# Finale_Competition.net
KiCad netlist of a schematic drawn in Altium Designer
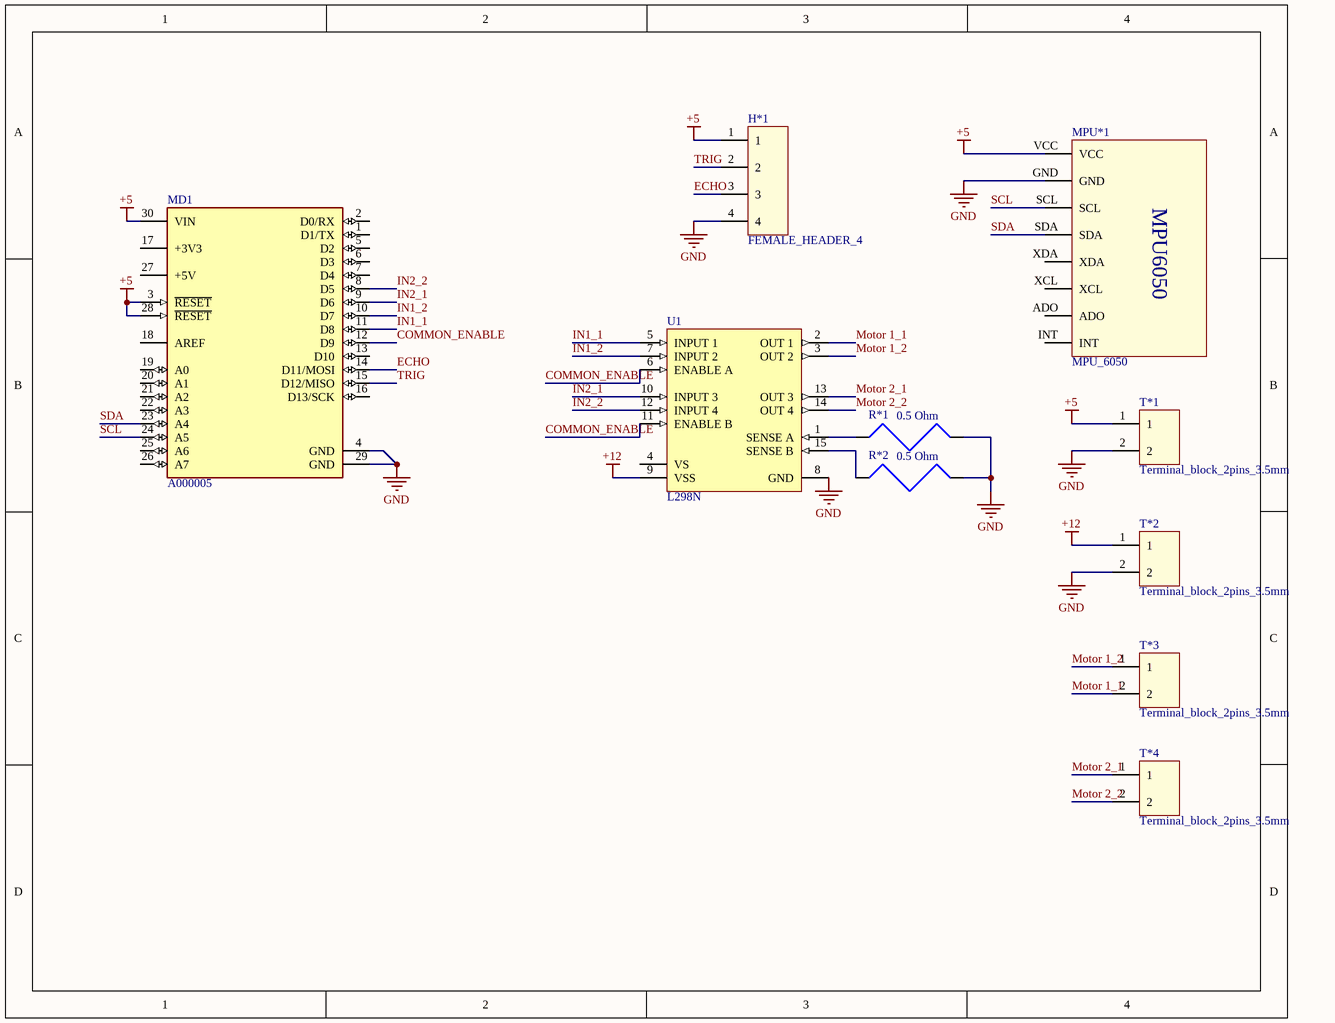
[diagram p0: Finale_Competition.SchDoc]

(export (version "E")
  (design (tool "Eeschema 10.0.6"))
  (components
    (comp (ref "H*1")
      (value "FEMALE_HEADER_4")
      (footprint "Female_Header_4")
      (libsource (lib "Mia_Training") (part "FEMALE_HEADER_4"))
    )
    (comp (ref "MD1")
      (value "A000005")
      (footprint "FP-A000005-MFG")
      (description "ARDUINO NANO ATMEGA328 EVAL BRD")
      (libsource (lib "Altium Content Vault") (part "d190c066e99afd1c6882cf92e11b2cc"))
    )
    (comp (ref "MPU*1")
      (value "MPU_6050")
      (footprint "MPU6050")
      (libsource (lib "Mia_Training") (part "MPU_6050"))
    )
    (comp (ref "R*1")
      (value "0.5 Ohm")
      (footprint "Resistor")
      (libsource (lib "Mia_Training") (part "Resistor"))
    )
    (comp (ref "R*2")
      (value "0.5 Ohm")
      (footprint "Resistor")
      (libsource (lib "Mia_Training") (part "Resistor"))
    )
    (comp (ref "T*1")
      (value "Terminal_block_2pins_3.5mm")
      (footprint "Terminal_block_2pins_3.5mm")
      (libsource (lib "Mia_Training") (part "Terminal_block_2pins_3.5mm"))
    )
    (comp (ref "T*2")
      (value "Terminal_block_2pins_3.5mm")
      (footprint "Terminal_block_2pins_3.5mm")
      (libsource (lib "Mia_Training") (part "Terminal_block_2pins_3.5mm"))
    )
    (comp (ref "T*3")
      (value "Terminal_block_2pins_3.5mm")
      (footprint "Terminal_block_2pins_3.5mm")
      (libsource (lib "Mia_Training") (part "Terminal_block_2pins_3.5mm"))
    )
    (comp (ref "T*4")
      (value "Terminal_block_2pins_3.5mm")
      (footprint "Terminal_block_2pins_3.5mm")
      (libsource (lib "Mia_Training") (part "Terminal_block_2pins_3.5mm"))
    )
    (comp (ref "U1")
      (value "L298N")
      (footprint "STM-FM-15")
      (description "Dual Full-Bridge Driver, 4.8 to 46 V, -40 to 150 degC, 15-Pin FM (MW 15L), RoHS, Tube")
      (fields (field (name "MANUFACTURER") "STMicroelectronics") (field (name "PARTNUMBER") "L298"))
      (libsource (lib "Altium Content Vault") (part "STM-L298-15"))
    )
  )
  (nets
    (net (code "1") (name "+5") (class "Default")
      (node (ref "H*1") (pin "1") (pinfunction "1_1") (pintype "passive"))
      (node (ref "MD1") (pin "28") (pinfunction "~{RESET}_28") (pintype "input"))
      (node (ref "MD1") (pin "3") (pinfunction "~{RESET}_3") (pintype "input"))
      (node (ref "MD1") (pin "30") (pinfunction "VIN_30") (pintype "power_in"))
      (node (ref "MPU*1") (pin "VCC") (pinfunction "VCC_VCC") (pintype "passive"))
      (node (ref "T*1") (pin "1") (pinfunction "1_1") (pintype "passive"))
    )
    (net (code "2") (name "+12") (class "Default")
      (node (ref "T*2") (pin "1") (pinfunction "1_1") (pintype "passive"))
      (node (ref "U1") (pin "9") (pinfunction "VSS_9") (pintype "power_in"))
    )
    (net (code "3") (name "/COMMON_ENABLE") (class "Default")
      (node (ref "MD1") (pin "12") (pinfunction "D9_12") (pintype "bidirectional"))
      (node (ref "U1") (pin "11") (pinfunction "ENABLE_B_11") (pintype "input"))
      (node (ref "U1") (pin "6") (pinfunction "ENABLE_A_6") (pintype "input"))
    )
    (net (code "4") (name "/ECHO") (class "Default")
      (node (ref "H*1") (pin "3") (pinfunction "3_3") (pintype "passive"))
      (node (ref "MD1") (pin "14") (pinfunction "D11/MOSI_14") (pintype "bidirectional"))
    )
    (net (code "5") (name "/IN1_1") (class "Default")
      (node (ref "MD1") (pin "11") (pinfunction "D8_11") (pintype "bidirectional"))
      (node (ref "U1") (pin "5") (pinfunction "INPUT_1_5") (pintype "input"))
    )
    (net (code "6") (name "/IN1_2") (class "Default")
      (node (ref "MD1") (pin "10") (pinfunction "D7_10") (pintype "bidirectional"))
      (node (ref "U1") (pin "7") (pinfunction "INPUT_2_7") (pintype "input"))
    )
    (net (code "7") (name "/IN2_1") (class "Default")
      (node (ref "MD1") (pin "9") (pinfunction "D6_9") (pintype "bidirectional"))
      (node (ref "U1") (pin "10") (pinfunction "INPUT_3_10") (pintype "input"))
    )
    (net (code "8") (name "/IN2_2") (class "Default")
      (node (ref "MD1") (pin "8") (pinfunction "D5_8") (pintype "bidirectional"))
      (node (ref "U1") (pin "12") (pinfunction "INPUT_4_12") (pintype "input"))
    )
    (net (code "9") (name "/Motor 1_1") (class "Default")
      (node (ref "T*3") (pin "2") (pinfunction "2_2") (pintype "passive"))
      (node (ref "U1") (pin "2") (pinfunction "OUT_1_2") (pintype "output"))
    )
    (net (code "10") (name "/Motor 1_2") (class "Default")
      (node (ref "T*3") (pin "1") (pinfunction "1_1") (pintype "passive"))
      (node (ref "U1") (pin "3") (pinfunction "OUT_2_3") (pintype "output"))
    )
    (net (code "11") (name "/Motor 2_1") (class "Default")
      (node (ref "T*4") (pin "1") (pinfunction "1_1") (pintype "passive"))
      (node (ref "U1") (pin "13") (pinfunction "OUT_3_13") (pintype "output"))
    )
    (net (code "12") (name "/Motor 2_2") (class "Default")
      (node (ref "T*4") (pin "2") (pinfunction "2_2") (pintype "passive"))
      (node (ref "U1") (pin "14") (pinfunction "OUT_4_14") (pintype "output"))
    )
    (net (code "13") (name "/SCL") (class "Default")
      (node (ref "MD1") (pin "24") (pinfunction "A5_24") (pintype "bidirectional"))
      (node (ref "MPU*1") (pin "SCL") (pinfunction "SCL_SCL") (pintype "passive"))
    )
    (net (code "14") (name "/SDA") (class "Default")
      (node (ref "MD1") (pin "23") (pinfunction "A4_23") (pintype "bidirectional"))
      (node (ref "MPU*1") (pin "SDA") (pinfunction "SDA_SDA") (pintype "passive"))
    )
    (net (code "15") (name "/TRIG") (class "Default")
      (node (ref "H*1") (pin "2") (pinfunction "2_2") (pintype "passive"))
      (node (ref "MD1") (pin "15") (pinfunction "D12/MISO_15") (pintype "bidirectional"))
    )
    (net (code "16") (name "GND") (class "Default")
      (node (ref "H*1") (pin "4") (pinfunction "4_4") (pintype "passive"))
      (node (ref "MD1") (pin "29") (pinfunction "GND_29") (pintype "power_in"))
      (node (ref "MD1") (pin "4") (pinfunction "GND_4") (pintype "power_in"))
      (node (ref "MPU*1") (pin "GND") (pinfunction "GND_GND") (pintype "passive"))
      (node (ref "R*1") (pin "2") (pinfunction "2_2") (pintype "passive"))
      (node (ref "R*2") (pin "2") (pinfunction "2_2") (pintype "passive"))
      (node (ref "T*1") (pin "2") (pinfunction "2_2") (pintype "passive"))
      (node (ref "T*2") (pin "2") (pinfunction "2_2") (pintype "passive"))
      (node (ref "U1") (pin "8") (pinfunction "GND_8") (pintype "power_in"))
    )
    (net (code "17") (name "Net-(U1-SENSE_A)") (class "Default")
      (node (ref "R*1") (pin "1") (pinfunction "1_1") (pintype "passive"))
      (node (ref "U1") (pin "1") (pinfunction "SENSE_A_1") (pintype "input"))
    )
    (net (code "18") (name "Net-(U1-SENSE_B)") (class "Default")
      (node (ref "R*2") (pin "1") (pinfunction "1_1") (pintype "passive"))
      (node (ref "U1") (pin "15") (pinfunction "SENSE_B_15") (pintype "input"))
    )
    (net (code "19") (name "unconnected-(MD1-+3V3-Pad17)") (class "Default")
      (node (ref "MD1") (pin "17") (pinfunction "+3V3_17") (pintype "power_in"))
    )
    (net (code "20") (name "unconnected-(MD1-+5V-Pad27)") (class "Default")
      (node (ref "MD1") (pin "27") (pinfunction "+5V_27") (pintype "power_in"))
    )
    (net (code "21") (name "unconnected-(MD1-A0-Pad19)") (class "Default")
      (node (ref "MD1") (pin "19") (pinfunction "A0_19") (pintype "bidirectional"))
    )
    (net (code "22") (name "unconnected-(MD1-A1-Pad20)") (class "Default")
      (node (ref "MD1") (pin "20") (pinfunction "A1_20") (pintype "bidirectional"))
    )
    (net (code "23") (name "unconnected-(MD1-A2-Pad21)") (class "Default")
      (node (ref "MD1") (pin "21") (pinfunction "A2_21") (pintype "bidirectional"))
    )
    (net (code "24") (name "unconnected-(MD1-A3-Pad22)") (class "Default")
      (node (ref "MD1") (pin "22") (pinfunction "A3_22") (pintype "bidirectional"))
    )
    (net (code "25") (name "unconnected-(MD1-A6-Pad25)") (class "Default")
      (node (ref "MD1") (pin "25") (pinfunction "A6_25") (pintype "bidirectional"))
    )
    (net (code "26") (name "unconnected-(MD1-A7-Pad26)") (class "Default")
      (node (ref "MD1") (pin "26") (pinfunction "A7_26") (pintype "bidirectional"))
    )
    (net (code "27") (name "unconnected-(MD1-AREF-Pad18)") (class "Default")
      (node (ref "MD1") (pin "18") (pinfunction "AREF_18") (pintype "passive"))
    )
    (net (code "28") (name "unconnected-(MD1-D0{slash}RX-Pad2)") (class "Default")
      (node (ref "MD1") (pin "2") (pinfunction "D0/RX_2") (pintype "bidirectional"))
    )
    (net (code "29") (name "unconnected-(MD1-D1{slash}TX-Pad1)") (class "Default")
      (node (ref "MD1") (pin "1") (pinfunction "D1/TX_1") (pintype "bidirectional"))
    )
    (net (code "30") (name "unconnected-(MD1-D2-Pad5)") (class "Default")
      (node (ref "MD1") (pin "5") (pinfunction "D2_5") (pintype "bidirectional"))
    )
    (net (code "31") (name "unconnected-(MD1-D3-Pad6)") (class "Default")
      (node (ref "MD1") (pin "6") (pinfunction "D3_6") (pintype "bidirectional"))
    )
    (net (code "32") (name "unconnected-(MD1-D4-Pad7)") (class "Default")
      (node (ref "MD1") (pin "7") (pinfunction "D4_7") (pintype "bidirectional"))
    )
    (net (code "33") (name "unconnected-(MD1-D10-Pad13)") (class "Default")
      (node (ref "MD1") (pin "13") (pinfunction "D10_13") (pintype "bidirectional"))
    )
    (net (code "34") (name "unconnected-(MD1-D13{slash}SCK-Pad16)") (class "Default")
      (node (ref "MD1") (pin "16") (pinfunction "D13/SCK_16") (pintype "bidirectional"))
    )
    (net (code "35") (name "unconnected-(MPU*1-PadADO)") (class "Default")
      (node (ref "MPU*1") (pin "ADO") (pinfunction "ADO_ADO") (pintype "passive"))
    )
    (net (code "36") (name "unconnected-(MPU*1-PadINT)") (class "Default")
      (node (ref "MPU*1") (pin "INT") (pinfunction "INT_INT") (pintype "passive"))
    )
    (net (code "37") (name "unconnected-(MPU*1-PadXCL)") (class "Default")
      (node (ref "MPU*1") (pin "XCL") (pinfunction "XCL_XCL") (pintype "passive"))
    )
    (net (code "38") (name "unconnected-(MPU*1-PadXDA)") (class "Default")
      (node (ref "MPU*1") (pin "XDA") (pinfunction "XDA_XDA") (pintype "passive"))
    )
    (net (code "39") (name "unconnected-(U1-VS-Pad4)") (class "Default")
      (node (ref "U1") (pin "4") (pinfunction "VS_4") (pintype "power_in"))
    )
  )
)
